# AXAWIFI.net
KiCad netlist of a schematic drawn in EAGLE
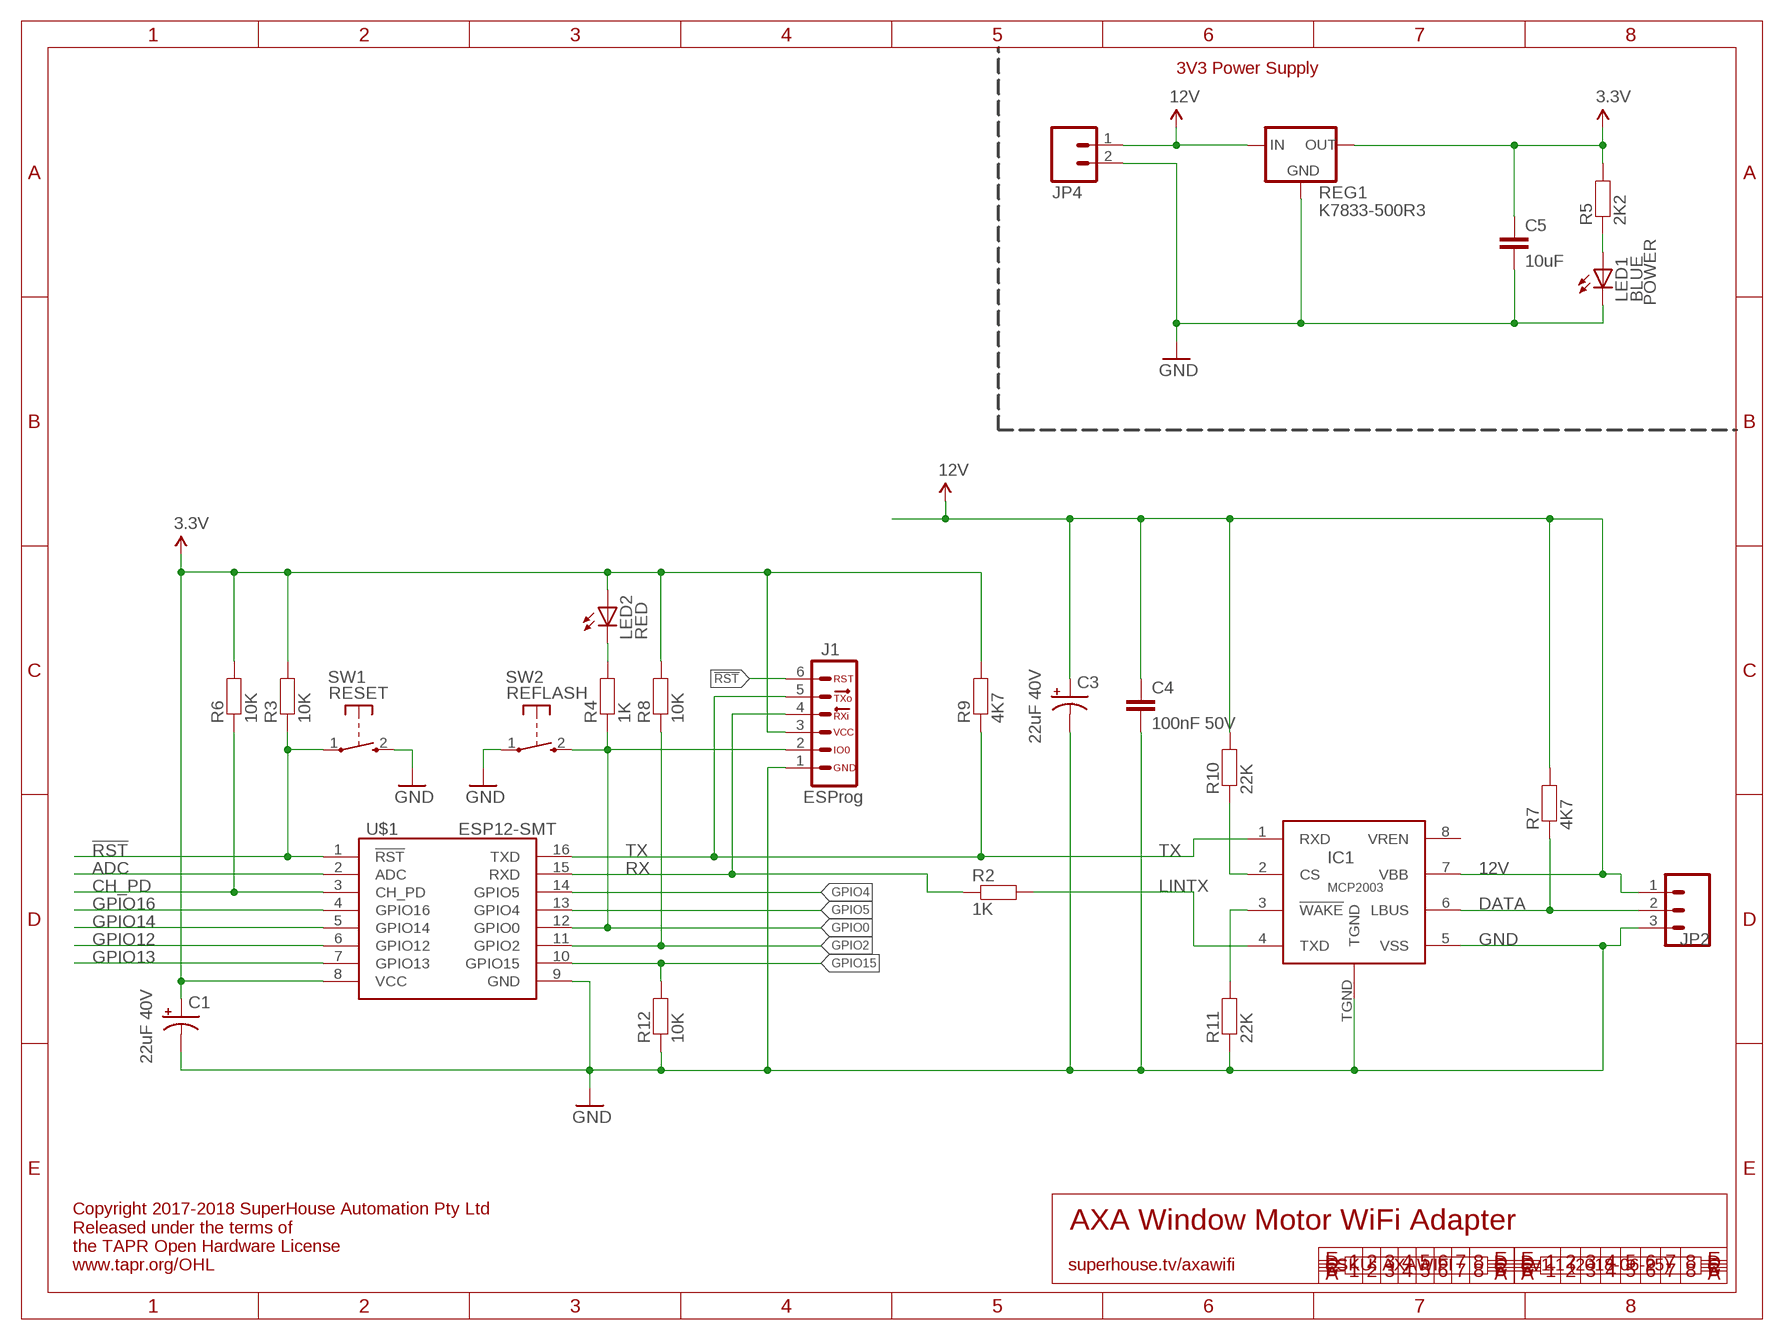
[diagram p0: schematic, sheet 1]

(export (version "E")
  (design (tool "Eeschema 10.0.6"))
  (components
    (comp (ref "C1")
      (value "22uF 40V")
      (footprint "eagle-import:PANASONIC_C")
      (libsource (lib "eagle-import") (part "CAP_POLC"))
    )
    (comp (ref "C3")
      (value "22uF 40V")
      (footprint "eagle-import:PANASONIC_C")
      (libsource (lib "eagle-import") (part "CAP_POLC"))
    )
    (comp (ref "C4")
      (value "100nF 50V")
      (footprint "eagle-import:C0603")
      (libsource (lib "eagle-import") (part "CAP0603"))
    )
    (comp (ref "C5")
      (value "10uF")
      (footprint "eagle-import:C0805")
      (libsource (lib "eagle-import") (part "CAP0805"))
    )
    (comp (ref "IC1")
      (value "MCP2003")
      (footprint "eagle-import:SOIC8T")
      (libsource (lib "eagle-import") (part "MCP2003"))
    )
    (comp (ref "J1")
      (value "ESPROG-SOCKET")
      (footprint "eagle-import:ESPROG-S")
      (libsource (lib "eagle-import") (part "ESPROG-SOCKET"))
    )
    (comp (ref "JP2")
      (value "M03-PLAIN")
      (footprint "eagle-import:1X03")
      (libsource (lib "eagle-import") (part "M03-PLAIN"))
    )
    (comp (ref "JP4")
      (value "M02-SCREW-3.5MM")
      (footprint "eagle-import:SCREWTERMINAL-3.5MM-2")
      (libsource (lib "eagle-import") (part "M02-SCREW-3.5MM"))
    )
    (comp (ref "LED1")
      (value "BLUE")
      (footprint "eagle-import:LED-0603")
      (libsource (lib "eagle-import") (part "LED0603"))
    )
    (comp (ref "LED2")
      (value "RED")
      (footprint "eagle-import:LED-0603")
      (libsource (lib "eagle-import") (part "LED0603"))
    )
    (comp (ref "R2")
      (value "1K")
      (footprint "eagle-import:R0603")
      (libsource (lib "eagle-import") (part "RESISTOR0603"))
    )
    (comp (ref "R3")
      (value "10K")
      (footprint "eagle-import:R0603")
      (libsource (lib "eagle-import") (part "RESISTOR0603"))
    )
    (comp (ref "R4")
      (value "1K")
      (footprint "eagle-import:R0603")
      (libsource (lib "eagle-import") (part "RESISTOR0603"))
    )
    (comp (ref "R5")
      (value "2K2")
      (footprint "eagle-import:R0603")
      (libsource (lib "eagle-import") (part "RESISTOR0603"))
    )
    (comp (ref "R6")
      (value "10K")
      (footprint "eagle-import:R0603")
      (libsource (lib "eagle-import") (part "RESISTOR0603"))
    )
    (comp (ref "R7")
      (value "4K7")
      (footprint "eagle-import:R0603")
      (libsource (lib "eagle-import") (part "RESISTOR0603"))
    )
    (comp (ref "R8")
      (value "10K")
      (footprint "eagle-import:R0603")
      (libsource (lib "eagle-import") (part "RESISTOR0603"))
    )
    (comp (ref "R9")
      (value "4K7")
      (footprint "eagle-import:R0603")
      (libsource (lib "eagle-import") (part "RESISTOR0603"))
    )
    (comp (ref "R10")
      (value "22K")
      (footprint "eagle-import:R0603")
      (libsource (lib "eagle-import") (part "RESISTOR0603"))
    )
    (comp (ref "R11")
      (value "22K")
      (footprint "eagle-import:R0603")
      (libsource (lib "eagle-import") (part "RESISTOR0603"))
    )
    (comp (ref "R12")
      (value "10K")
      (footprint "eagle-import:R0603")
      (libsource (lib "eagle-import") (part "RESISTOR0603"))
    )
    (comp (ref "REG1")
      (value "K7833-500R3")
      (footprint "eagle-import:K78XX-500R3")
      (libsource (lib "eagle-import") (part "K78XX-500R3"))
    )
    (comp (ref "SW1")
      (value "RESET")
      (footprint "eagle-import:TACTILE_SMT_3X4X2")
      (libsource (lib "eagle-import") (part "TAC_SWITCH_2PINSMT"))
    )
    (comp (ref "SW2")
      (value "REFLASH")
      (footprint "eagle-import:TACTILE_SMT_3X4X2")
      (libsource (lib "eagle-import") (part "TAC_SWITCH_2PINSMT"))
    )
    (comp (ref "U$1")
      (value "ESP12-SMT")
      (footprint "eagle-import:ESP12")
      (libsource (lib "eagle-import") (part "ESP12-SMT"))
    )
  )
  (nets
    (net (code "1") (name "/ADC") (class "Default")
      (node (ref "U$1") (pin "2") (pinfunction "ADC_2") (pintype "input"))
    )
    (net (code "2") (name "/CH_PD") (class "Default")
      (node (ref "R6") (pin "1") (pinfunction "1_1") (pintype "passive"))
      (node (ref "U$1") (pin "3") (pinfunction "CH_PD_3") (pintype "input"))
    )
    (net (code "3") (name "/DATA") (class "Default")
      (node (ref "IC1") (pin "6") (pinfunction "LBUS_6") (pintype "bidirectional"))
      (node (ref "JP2") (pin "2") (pinfunction "2_2") (pintype "passive"))
      (node (ref "R7") (pin "1") (pinfunction "1_1") (pintype "passive"))
    )
    (net (code "4") (name "/GPIO12") (class "Default")
      (node (ref "U$1") (pin "6") (pinfunction "GPIO12_6") (pintype "bidirectional"))
    )
    (net (code "5") (name "/GPIO13") (class "Default")
      (node (ref "U$1") (pin "7") (pinfunction "GPIO13_7") (pintype "bidirectional"))
    )
    (net (code "6") (name "/GPIO14") (class "Default")
      (node (ref "U$1") (pin "5") (pinfunction "GPIO14_5") (pintype "bidirectional"))
    )
    (net (code "7") (name "/GPIO16") (class "Default")
      (node (ref "U$1") (pin "4") (pinfunction "GPIO16_4") (pintype "bidirectional"))
    )
    (net (code "8") (name "/LINTX") (class "Default")
      (node (ref "IC1") (pin "4") (pinfunction "TXD_4") (pintype "output"))
      (node (ref "R2") (pin "2") (pinfunction "2_2") (pintype "passive"))
    )
    (net (code "9") (name "/RX") (class "Default")
      (node (ref "J1") (pin "4") (pinfunction "4_4") (pintype "passive"))
      (node (ref "R2") (pin "1") (pinfunction "1_1") (pintype "passive"))
      (node (ref "U$1") (pin "15") (pinfunction "RXD_15") (pintype "input"))
    )
    (net (code "10") (name "/TX") (class "Default")
      (node (ref "IC1") (pin "1") (pinfunction "RXD_1") (pintype "input"))
      (node (ref "J1") (pin "5") (pinfunction "5_5") (pintype "passive"))
      (node (ref "R9") (pin "1") (pinfunction "1_1") (pintype "passive"))
      (node (ref "U$1") (pin "16") (pinfunction "TXD_16") (pintype "output"))
    )
    (net (code "11") (name "/~{RST}") (class "Default")
      (node (ref "J1") (pin "6") (pinfunction "6_6") (pintype "passive"))
      (node (ref "R3") (pin "1") (pinfunction "1_1") (pintype "passive"))
      (node (ref "SW1") (pin "1") (pinfunction "P_1") (pintype "passive"))
      (node (ref "U$1") (pin "1") (pinfunction "~{RST}_1") (pintype "bidirectional"))
    )
    (net (code "12") (name "3.3V") (class "Default")
      (node (ref "C1") (pin "+") (pinfunction "+_+") (pintype "passive"))
      (node (ref "C5") (pin "1") (pinfunction "1_1") (pintype "passive"))
      (node (ref "J1") (pin "3") (pinfunction "3_3") (pintype "passive"))
      (node (ref "LED2") (pin "A") (pinfunction "A_A") (pintype "passive"))
      (node (ref "R3") (pin "2") (pinfunction "2_2") (pintype "passive"))
      (node (ref "R5") (pin "2") (pinfunction "2_2") (pintype "passive"))
      (node (ref "R6") (pin "2") (pinfunction "2_2") (pintype "passive"))
      (node (ref "R8") (pin "2") (pinfunction "2_2") (pintype "passive"))
      (node (ref "R9") (pin "2") (pinfunction "2_2") (pintype "passive"))
      (node (ref "REG1") (pin "3") (pinfunction "OUT_3") (pintype "output"))
      (node (ref "U$1") (pin "8") (pinfunction "VCC_8") (pintype "power_in"))
    )
    (net (code "13") (name "12V") (class "Default")
      (node (ref "C3") (pin "+") (pinfunction "+_+") (pintype "passive"))
      (node (ref "C4") (pin "1") (pinfunction "1_1") (pintype "passive"))
      (node (ref "IC1") (pin "7") (pinfunction "VBB_7") (pintype "power_in"))
      (node (ref "JP2") (pin "1") (pinfunction "1_1") (pintype "passive"))
      (node (ref "JP4") (pin "1") (pinfunction "1_1") (pintype "passive"))
      (node (ref "R10") (pin "2") (pinfunction "2_2") (pintype "passive"))
      (node (ref "R7") (pin "2") (pinfunction "2_2") (pintype "passive"))
      (node (ref "REG1") (pin "1") (pinfunction "IN_1") (pintype "input"))
    )
    (net (code "14") (name "GND") (class "Default")
      (node (ref "C1") (pin "-") (pinfunction "-_-") (pintype "passive"))
      (node (ref "C3") (pin "-") (pinfunction "-_-") (pintype "passive"))
      (node (ref "C4") (pin "2") (pinfunction "2_2") (pintype "passive"))
      (node (ref "C5") (pin "2") (pinfunction "2_2") (pintype "passive"))
      (node (ref "IC1") (pin "5") (pinfunction "VSS_5") (pintype "power_in"))
      (node (ref "IC1") (pin "TGND") (pinfunction "TGND_TGND") (pintype "power_in"))
      (node (ref "J1") (pin "1") (pinfunction "1_1") (pintype "passive"))
      (node (ref "JP2") (pin "3") (pinfunction "3_3") (pintype "passive"))
      (node (ref "JP4") (pin "2") (pinfunction "2_2") (pintype "passive"))
      (node (ref "LED1") (pin "C") (pinfunction "C_C") (pintype "passive"))
      (node (ref "R11") (pin "1") (pinfunction "1_1") (pintype "passive"))
      (node (ref "R12") (pin "1") (pinfunction "1_1") (pintype "passive"))
      (node (ref "REG1") (pin "2") (pinfunction "GND_2") (pintype "input"))
      (node (ref "SW1") (pin "2") (pinfunction "S_2") (pintype "passive"))
      (node (ref "SW2") (pin "1") (pinfunction "P_1") (pintype "passive"))
      (node (ref "U$1") (pin "9") (pinfunction "GND_9") (pintype "power_in"))
    )
    (net (code "15") (name "GPIO0") (class "Default")
      (node (ref "J1") (pin "2") (pinfunction "2_2") (pintype "passive"))
      (node (ref "R4") (pin "1") (pinfunction "1_1") (pintype "passive"))
      (node (ref "SW2") (pin "2") (pinfunction "S_2") (pintype "passive"))
      (node (ref "U$1") (pin "12") (pinfunction "GPIO0_12") (pintype "bidirectional"))
    )
    (net (code "16") (name "GPIO2") (class "Default")
      (node (ref "R8") (pin "1") (pinfunction "1_1") (pintype "passive"))
      (node (ref "U$1") (pin "11") (pinfunction "GPIO2_11") (pintype "bidirectional"))
    )
    (net (code "17") (name "GPIO4") (class "Default")
      (node (ref "U$1") (pin "14") (pinfunction "GPIO5_14") (pintype "bidirectional"))
    )
    (net (code "18") (name "GPIO5") (class "Default")
      (node (ref "U$1") (pin "13") (pinfunction "GPIO4_13") (pintype "bidirectional"))
    )
    (net (code "19") (name "GPIO15") (class "Default")
      (node (ref "R12") (pin "2") (pinfunction "2_2") (pintype "passive"))
      (node (ref "U$1") (pin "10") (pinfunction "GPIO15_10") (pintype "bidirectional"))
    )
    (net (code "20") (name "Net-(IC1-CS)") (class "Default")
      (node (ref "IC1") (pin "2") (pinfunction "CS_2") (pintype "input"))
      (node (ref "R10") (pin "1") (pinfunction "1_1") (pintype "passive"))
    )
    (net (code "21") (name "Net-(IC1-~{WAKE})") (class "Default")
      (node (ref "IC1") (pin "3") (pinfunction "~{WAKE}_3") (pintype "input"))
      (node (ref "R11") (pin "2") (pinfunction "2_2") (pintype "passive"))
    )
    (net (code "22") (name "Net-(LED1-PadA)") (class "Default")
      (node (ref "LED1") (pin "A") (pinfunction "A_A") (pintype "passive"))
      (node (ref "R5") (pin "1") (pinfunction "1_1") (pintype "passive"))
    )
    (net (code "23") (name "Net-(LED2-PadC)") (class "Default")
      (node (ref "LED2") (pin "C") (pinfunction "C_C") (pintype "passive"))
      (node (ref "R4") (pin "2") (pinfunction "2_2") (pintype "passive"))
    )
    (net (code "24") (name "unconnected-(IC1-VREN-Pad8)") (class "Default")
      (node (ref "IC1") (pin "8") (pinfunction "VREN_8") (pintype "output"))
    )
  )
)
